# Air_Quality_Sensor_V1_0.net
KiCad netlist of a schematic drawn in EAGLE
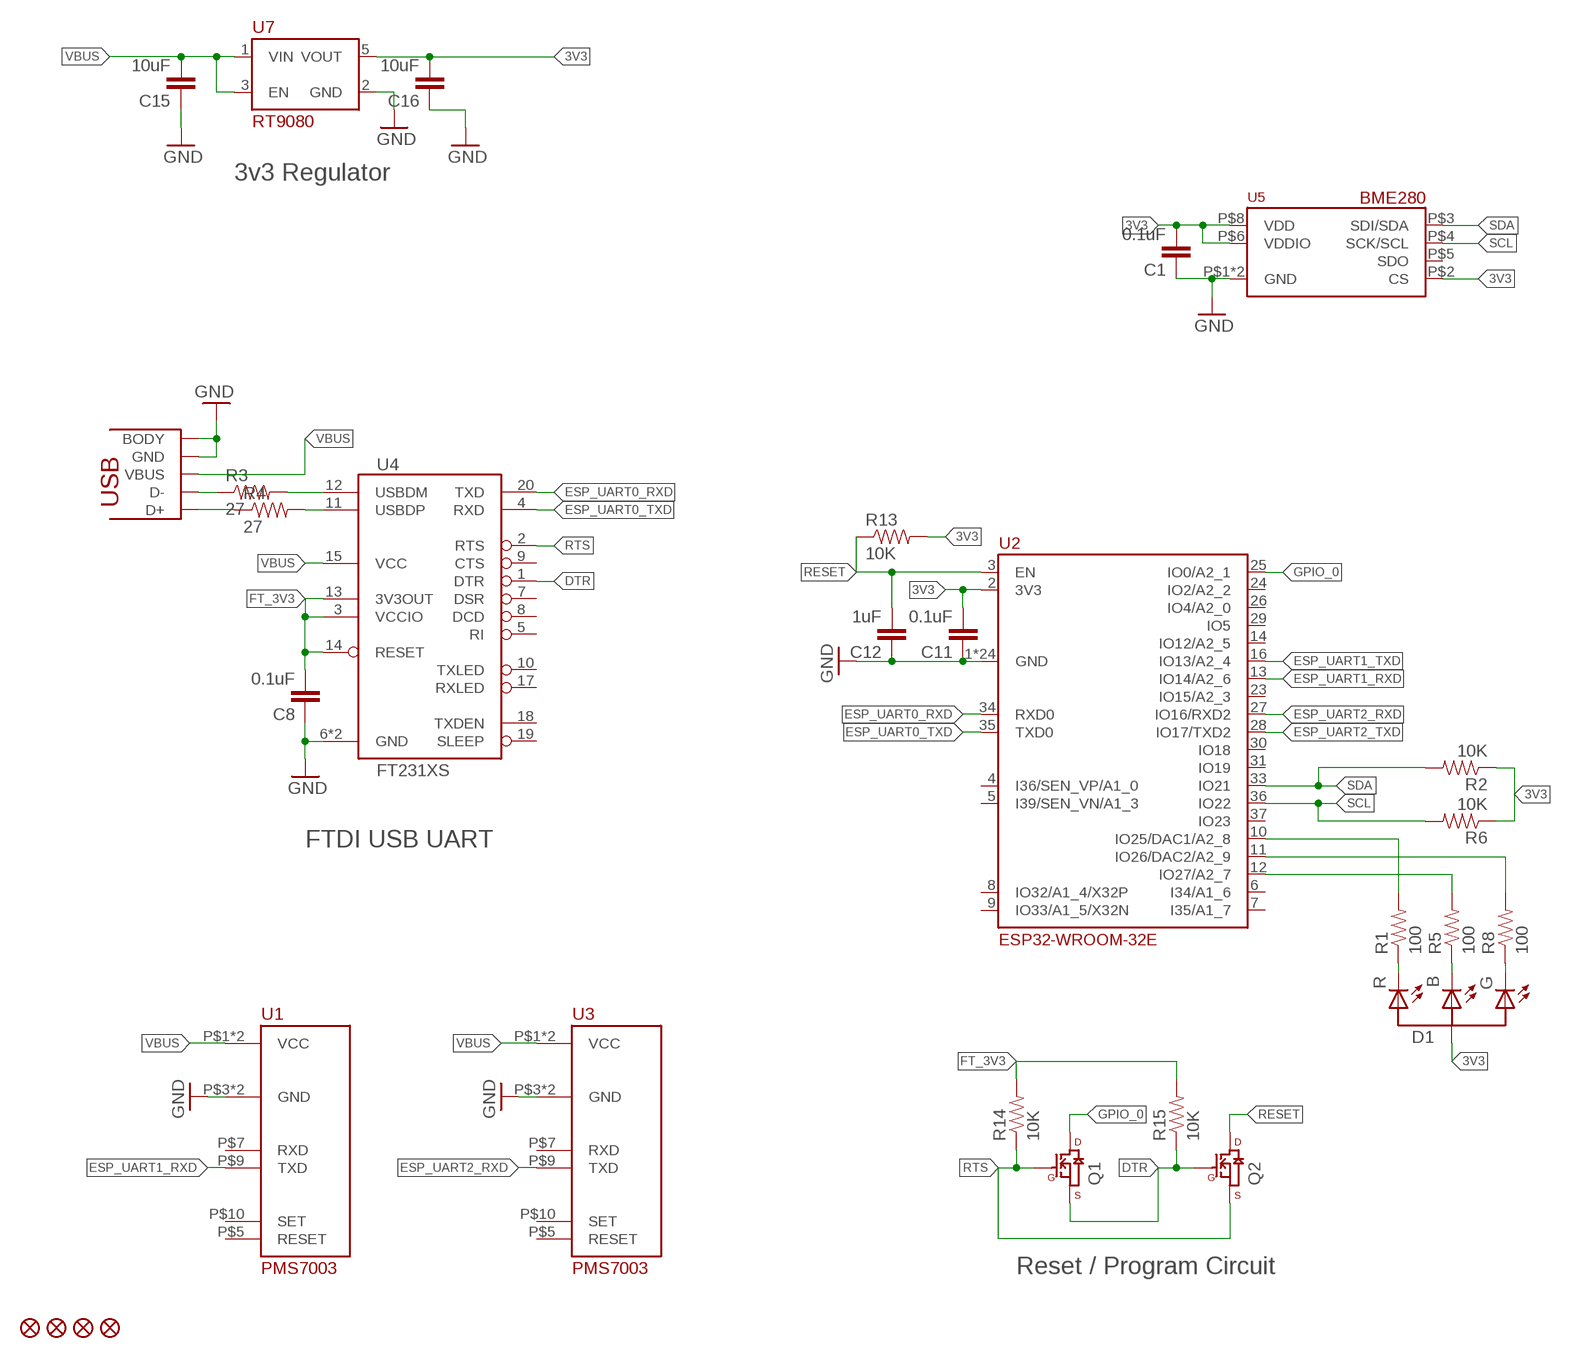
[diagram p0: schematic, sheet 1]

(export (version "E")
  (design (tool "Eeschema 10.0.6"))
  (components
    (comp (ref "C1")
      (value "0.1uF")
      (footprint "eagle-import:0603-CAP")
      (libsource (lib "eagle-import") (part "CAP0603-CAP"))
    )
    (comp (ref "C8")
      (value "0.1uF")
      (footprint "eagle-import:0603-CAP")
      (libsource (lib "eagle-import") (part "CAP0603-CAP"))
    )
    (comp (ref "C11")
      (value "0.1uF")
      (footprint "eagle-import:0603-CAP")
      (libsource (lib "eagle-import") (part "CAP0603-CAP"))
    )
    (comp (ref "C12")
      (value "1uF")
      (footprint "eagle-import:0603-CAP")
      (libsource (lib "eagle-import") (part "CAP0603-CAP"))
    )
    (comp (ref "C15")
      (value "10uF")
      (footprint "eagle-import:1206")
      (libsource (lib "eagle-import") (part "CAP1206"))
    )
    (comp (ref "C16")
      (value "10uF")
      (footprint "eagle-import:1206")
      (libsource (lib "eagle-import") (part "CAP1206"))
    )
    (comp (ref "D1")
      (value "LED_TRICOLOR_COM-ANODE")
      (footprint "eagle-import:LED_1206_SIDE_TRICOLOR")
      (libsource (lib "eagle-import") (part "LED_TRICOLOR_COM-ANODE"))
    )
    (comp (ref "FID1")
      (value "FIDUCIAL")
      (footprint "eagle-import:FIDUCIAL")
      (libsource (lib "eagle-import") (part "FIDUCIAL"))
    )
    (comp (ref "FID2")
      (value "FIDUCIAL")
      (footprint "eagle-import:FIDUCIAL")
      (libsource (lib "eagle-import") (part "FIDUCIAL"))
    )
    (comp (ref "FID3")
      (value "FIDUCIAL")
      (footprint "eagle-import:FIDUCIAL")
      (libsource (lib "eagle-import") (part "FIDUCIAL"))
    )
    (comp (ref "FID4")
      (value "FIDUCIAL")
      (footprint "eagle-import:FIDUCIAL")
      (libsource (lib "eagle-import") (part "FIDUCIAL"))
    )
    (comp (ref "Q1")
      (value "MOSFET_N_CHANNELSI1308")
      (footprint "eagle-import:SC-70-3")
      (libsource (lib "eagle-import") (part "MOSFET_N_CHANNELSI1308"))
    )
    (comp (ref "Q2")
      (value "MOSFET_N_CHANNELSI1308")
      (footprint "eagle-import:SC-70-3")
      (libsource (lib "eagle-import") (part "MOSFET_N_CHANNELSI1308"))
    )
    (comp (ref "R1")
      (value "100")
      (footprint "eagle-import:0603-RES")
      (libsource (lib "eagle-import") (part "RESISTOR0603-RES"))
    )
    (comp (ref "R2")
      (value "10K")
      (footprint "eagle-import:0603-RES")
      (libsource (lib "eagle-import") (part "RESISTOR0603-RES"))
    )
    (comp (ref "R3")
      (value "27")
      (footprint "eagle-import:0603-RES")
      (libsource (lib "eagle-import") (part "RESISTOR0603-RES"))
    )
    (comp (ref "R4")
      (value "27")
      (footprint "eagle-import:0603-RES")
      (libsource (lib "eagle-import") (part "RESISTOR0603-RES"))
    )
    (comp (ref "R5")
      (value "100")
      (footprint "eagle-import:0603-RES")
      (libsource (lib "eagle-import") (part "RESISTOR0603-RES"))
    )
    (comp (ref "R6")
      (value "10K")
      (footprint "eagle-import:0603-RES")
      (libsource (lib "eagle-import") (part "RESISTOR0603-RES"))
    )
    (comp (ref "R8")
      (value "100")
      (footprint "eagle-import:0603-RES")
      (libsource (lib "eagle-import") (part "RESISTOR0603-RES"))
    )
    (comp (ref "R13")
      (value "10K")
      (footprint "eagle-import:0603-RES")
      (libsource (lib "eagle-import") (part "RESISTOR0603-RES"))
    )
    (comp (ref "R14")
      (value "10K")
      (footprint "eagle-import:0603-RES")
      (libsource (lib "eagle-import") (part "RESISTOR0603-RES"))
    )
    (comp (ref "R15")
      (value "10K")
      (footprint "eagle-import:0603-RES")
      (libsource (lib "eagle-import") (part "RESISTOR0603-RES"))
    )
    (comp (ref "U$1")
      (value "USB-MICROB")
      (footprint "eagle-import:USB-MICROB-10118192")
      (libsource (lib "eagle-import") (part "USB-MICROB"))
    )
    (comp (ref "U1")
      (value "PMS7003_SMD")
      (footprint "eagle-import:PMS7003_SMD")
      (libsource (lib "eagle-import") (part "PMS7003_SMD"))
    )
    (comp (ref "U2")
      (value "ESP32-WROOM-32E")
      (footprint "eagle-import:ESP32-WROOM-32E")
      (libsource (lib "eagle-import") (part "ESP32-WROOM-32E"))
    )
    (comp (ref "U3")
      (value "PMS7003_SMD")
      (footprint "eagle-import:PMS7003_SMD")
      (libsource (lib "eagle-import") (part "PMS7003_SMD"))
    )
    (comp (ref "U4")
      (value "FT231XS")
      (footprint "eagle-import:SSOP-20")
      (libsource (lib "eagle-import") (part "FT231XS"))
    )
    (comp (ref "U5")
      (value "BME280")
      (footprint "eagle-import:8-VFLGA")
      (libsource (lib "eagle-import") (part "BME280"))
    )
    (comp (ref "U7")
      (value "RT9080")
      (footprint "eagle-import:SOT-23-5")
      (libsource (lib "eagle-import") (part "RT9080"))
    )
  )
  (nets
    (net (code "1") (name "3V3") (class "Default")
      (node (ref "C1") (pin "2") (pinfunction "2_2") (pintype "passive"))
      (node (ref "C11") (pin "2") (pinfunction "2_2") (pintype "passive"))
      (node (ref "C16") (pin "2") (pinfunction "2_2") (pintype "passive"))
      (node (ref "D1") (pin "P$3") (pinfunction "A_P$3") (pintype "passive"))
      (node (ref "R13") (pin "2") (pinfunction "2_2") (pintype "passive"))
      (node (ref "R2") (pin "1") (pinfunction "1_1") (pintype "passive"))
      (node (ref "R6") (pin "1") (pinfunction "1_1") (pintype "passive"))
      (node (ref "U2") (pin "2") (pinfunction "3V3_2") (pintype "power_in"))
      (node (ref "U5") (pin "P$2") (pinfunction "CS_P$2") (pintype "bidirectional"))
      (node (ref "U5") (pin "P$6") (pinfunction "VDDIO_P$6") (pintype "bidirectional"))
      (node (ref "U5") (pin "P$8") (pinfunction "VDD_P$8") (pintype "bidirectional"))
      (node (ref "U7") (pin "5") (pinfunction "VOUT_5") (pintype "bidirectional"))
    )
    (net (code "2") (name "DTR") (class "Default")
      (node (ref "Q1") (pin "P$2") (pinfunction "S_P$2") (pintype "bidirectional"))
      (node (ref "Q2") (pin "P$1") (pinfunction "G_P$1") (pintype "bidirectional"))
      (node (ref "R15") (pin "1") (pinfunction "1_1") (pintype "passive"))
      (node (ref "U4") (pin "1") (pinfunction "DTR_1") (pintype "output"))
    )
    (net (code "3") (name "ESP_UART0_RXD") (class "Default")
      (node (ref "U2") (pin "34") (pinfunction "RXD0_34") (pintype "bidirectional"))
      (node (ref "U4") (pin "20") (pinfunction "TXD_20") (pintype "output"))
    )
    (net (code "4") (name "ESP_UART0_TXD") (class "Default")
      (node (ref "U2") (pin "35") (pinfunction "TXD0_35") (pintype "bidirectional"))
      (node (ref "U4") (pin "4") (pinfunction "RXD_4") (pintype "input"))
    )
    (net (code "5") (name "ESP_UART1_RXD") (class "Default")
      (node (ref "U1") (pin "P$9") (pinfunction "TXD_P$9") (pintype "bidirectional"))
      (node (ref "U2") (pin "13") (pinfunction "IO14/A2_6_13") (pintype "bidirectional"))
    )
    (net (code "6") (name "ESP_UART1_TXD") (class "Default")
      (node (ref "U2") (pin "16") (pinfunction "IO13/A2_4_16") (pintype "bidirectional"))
    )
    (net (code "7") (name "ESP_UART2_RXD") (class "Default")
      (node (ref "U2") (pin "27") (pinfunction "IO16/RXD2_27") (pintype "bidirectional"))
      (node (ref "U3") (pin "P$9") (pinfunction "TXD_P$9") (pintype "bidirectional"))
    )
    (net (code "8") (name "ESP_UART2_TXD") (class "Default")
      (node (ref "U2") (pin "28") (pinfunction "IO17/TXD2_28") (pintype "bidirectional"))
    )
    (net (code "9") (name "FT_3V3") (class "Default")
      (node (ref "C8") (pin "2") (pinfunction "2_2") (pintype "passive"))
      (node (ref "R14") (pin "2") (pinfunction "2_2") (pintype "passive"))
      (node (ref "R15") (pin "2") (pinfunction "2_2") (pintype "passive"))
      (node (ref "U4") (pin "13") (pinfunction "3V3OUT_13") (pintype "output"))
      (node (ref "U4") (pin "14") (pinfunction "RESET_14") (pintype "input"))
      (node (ref "U4") (pin "3") (pinfunction "VCCIO_3") (pintype "power_in"))
    )
    (net (code "10") (name "GND") (class "Default")
      (node (ref "C1") (pin "1") (pinfunction "1_1") (pintype "passive"))
      (node (ref "C11") (pin "1") (pinfunction "1_1") (pintype "passive"))
      (node (ref "C12") (pin "1") (pinfunction "1_1") (pintype "passive"))
      (node (ref "C15") (pin "1") (pinfunction "1_1") (pintype "passive"))
      (node (ref "C16") (pin "1") (pinfunction "1_1") (pintype "passive"))
      (node (ref "C8") (pin "1") (pinfunction "1_1") (pintype "passive"))
      (node (ref "U$1") (pin "5") (pinfunction "GND_5") (pintype "bidirectional"))
      (node (ref "U$1") (pin "BODY@1") (pinfunction "BODY_BODY@1") (pintype "bidirectional"))
      (node (ref "U$1") (pin "BODY@2") (pinfunction "BODY_BODY@2") (pintype "bidirectional"))
      (node (ref "U$1") (pin "BODY@3") (pinfunction "BODY_BODY@3") (pintype "bidirectional"))
      (node (ref "U$1") (pin "BODY@4") (pinfunction "BODY_BODY@4") (pintype "bidirectional"))
      (node (ref "U$1") (pin "BODY@5") (pinfunction "BODY_BODY@5") (pintype "bidirectional"))
      (node (ref "U$1") (pin "BODY@6") (pinfunction "BODY_BODY@6") (pintype "bidirectional"))
      (node (ref "U1") (pin "P$3") (pinfunction "GND_P$3") (pintype "bidirectional"))
      (node (ref "U1") (pin "P$4") (pinfunction "GND_P$4") (pintype "bidirectional"))
      (node (ref "U2") (pin "1") (pinfunction "GND_1") (pintype "power_in"))
      (node (ref "U2") (pin "15") (pinfunction "GND_15") (pintype "power_in"))
      (node (ref "U2") (pin "38") (pinfunction "GND_38") (pintype "power_in"))
      (node (ref "U2") (pin "P$1") (pinfunction "GND_P$1") (pintype "power_in"))
      (node (ref "U2") (pin "P$10") (pinfunction "GND_P$10") (pintype "power_in"))
      (node (ref "U2") (pin "P$11") (pinfunction "GND_P$11") (pintype "power_in"))
      (node (ref "U2") (pin "P$12") (pinfunction "GND_P$12") (pintype "power_in"))
      (node (ref "U2") (pin "P$2") (pinfunction "GND_P$2") (pintype "power_in"))
      (node (ref "U2") (pin "P$3") (pinfunction "GND_P$3") (pintype "power_in"))
      (node (ref "U2") (pin "P$4") (pinfunction "GND_P$4") (pintype "power_in"))
      (node (ref "U2") (pin "P$5") (pinfunction "GND_P$5") (pintype "power_in"))
      (node (ref "U2") (pin "P$6") (pinfunction "GND_P$6") (pintype "power_in"))
      (node (ref "U2") (pin "P$7") (pinfunction "GND_P$7") (pintype "power_in"))
      (node (ref "U2") (pin "P$8") (pinfunction "GND_P$8") (pintype "power_in"))
      (node (ref "U2") (pin "P$9") (pinfunction "GND_P$9") (pintype "power_in"))
      (node (ref "U2") (pin "PAD@1") (pinfunction "GND_PAD@1") (pintype "power_in"))
      (node (ref "U2") (pin "PAD@2") (pinfunction "GND_PAD@2") (pintype "power_in"))
      (node (ref "U2") (pin "PAD@3") (pinfunction "GND_PAD@3") (pintype "power_in"))
      (node (ref "U2") (pin "PAD@4") (pinfunction "GND_PAD@4") (pintype "power_in"))
      (node (ref "U2") (pin "PAD@5") (pinfunction "GND_PAD@5") (pintype "power_in"))
      (node (ref "U2") (pin "PAD@6") (pinfunction "GND_PAD@6") (pintype "power_in"))
      (node (ref "U2") (pin "PAD@7") (pinfunction "GND_PAD@7") (pintype "power_in"))
      (node (ref "U2") (pin "PAD@8") (pinfunction "GND_PAD@8") (pintype "power_in"))
      (node (ref "U2") (pin "PAD@9") (pinfunction "GND_PAD@9") (pintype "power_in"))
      (node (ref "U3") (pin "P$3") (pinfunction "GND_P$3") (pintype "bidirectional"))
      (node (ref "U3") (pin "P$4") (pinfunction "GND_P$4") (pintype "bidirectional"))
      (node (ref "U4") (pin "16") (pinfunction "GND_16") (pintype "power_in"))
      (node (ref "U4") (pin "6") (pinfunction "GND_6") (pintype "power_in"))
      (node (ref "U5") (pin "P$1") (pinfunction "GND_P$1") (pintype "bidirectional"))
      (node (ref "U5") (pin "P$7") (pinfunction "GND_P$7") (pintype "bidirectional"))
      (node (ref "U7") (pin "2") (pinfunction "GND_2") (pintype "bidirectional"))
    )
    (net (code "11") (name "GPIO_0") (class "Default")
      (node (ref "Q1") (pin "P$3") (pinfunction "D_P$3") (pintype "bidirectional"))
      (node (ref "U2") (pin "25") (pinfunction "IO0/A2_1_25") (pintype "bidirectional"))
    )
    (net (code "12") (name "Net-(D1-C_BLU)") (class "Default")
      (node (ref "D1") (pin "P$2") (pinfunction "C_BLU_P$2") (pintype "passive"))
      (node (ref "R5") (pin "1") (pinfunction "1_1") (pintype "passive"))
    )
    (net (code "13") (name "Net-(D1-C_GRN)") (class "Default")
      (node (ref "D1") (pin "P$1") (pinfunction "C_GRN_P$1") (pintype "passive"))
      (node (ref "R8") (pin "1") (pinfunction "1_1") (pintype "passive"))
    )
    (net (code "14") (name "Net-(D1-C_RED)") (class "Default")
      (node (ref "D1") (pin "P$4") (pinfunction "C_RED_P$4") (pintype "passive"))
      (node (ref "R1") (pin "1") (pinfunction "1_1") (pintype "passive"))
    )
    (net (code "15") (name "Net-(U$1-D+)") (class "Default")
      (node (ref "R4") (pin "1") (pinfunction "1_1") (pintype "passive"))
      (node (ref "U$1") (pin "3") (pinfunction "D+_3") (pintype "bidirectional"))
    )
    (net (code "16") (name "Net-(U$1-D-)") (class "Default")
      (node (ref "R3") (pin "1") (pinfunction "1_1") (pintype "passive"))
      (node (ref "U$1") (pin "2") (pinfunction "D-_2") (pintype "bidirectional"))
    )
    (net (code "17") (name "Net-(U2-IO25{slash}DAC1{slash}A2_8)") (class "Default")
      (node (ref "R1") (pin "2") (pinfunction "2_2") (pintype "passive"))
      (node (ref "U2") (pin "10") (pinfunction "IO25/DAC1/A2_8_10") (pintype "bidirectional"))
    )
    (net (code "18") (name "Net-(U2-IO26{slash}DAC2{slash}A2_9)") (class "Default")
      (node (ref "R8") (pin "2") (pinfunction "2_2") (pintype "passive"))
      (node (ref "U2") (pin "11") (pinfunction "IO26/DAC2/A2_9_11") (pintype "bidirectional"))
    )
    (net (code "19") (name "Net-(U2-IO27{slash}A2_7)") (class "Default")
      (node (ref "R5") (pin "2") (pinfunction "2_2") (pintype "passive"))
      (node (ref "U2") (pin "12") (pinfunction "IO27/A2_7_12") (pintype "bidirectional"))
    )
    (net (code "20") (name "Net-(U4-USBDM)") (class "Default")
      (node (ref "R3") (pin "2") (pinfunction "2_2") (pintype "passive"))
      (node (ref "U4") (pin "12") (pinfunction "USBDM_12") (pintype "bidirectional"))
    )
    (net (code "21") (name "Net-(U4-USBDP)") (class "Default")
      (node (ref "R4") (pin "2") (pinfunction "2_2") (pintype "passive"))
      (node (ref "U4") (pin "11") (pinfunction "USBDP_11") (pintype "bidirectional"))
    )
    (net (code "22") (name "RESET") (class "Default")
      (node (ref "C12") (pin "2") (pinfunction "2_2") (pintype "passive"))
      (node (ref "Q2") (pin "P$3") (pinfunction "D_P$3") (pintype "bidirectional"))
      (node (ref "R13") (pin "1") (pinfunction "1_1") (pintype "passive"))
      (node (ref "U2") (pin "3") (pinfunction "EN_3") (pintype "input"))
    )
    (net (code "23") (name "RTS") (class "Default")
      (node (ref "Q1") (pin "P$1") (pinfunction "G_P$1") (pintype "bidirectional"))
      (node (ref "Q2") (pin "P$2") (pinfunction "S_P$2") (pintype "bidirectional"))
      (node (ref "R14") (pin "1") (pinfunction "1_1") (pintype "passive"))
      (node (ref "U4") (pin "2") (pinfunction "RTS_2") (pintype "output"))
    )
    (net (code "24") (name "SCL") (class "Default")
      (node (ref "R6") (pin "2") (pinfunction "2_2") (pintype "passive"))
      (node (ref "U2") (pin "36") (pinfunction "IO22_36") (pintype "bidirectional"))
      (node (ref "U5") (pin "P$4") (pinfunction "SCK/SCL_P$4") (pintype "bidirectional"))
    )
    (net (code "25") (name "SDA") (class "Default")
      (node (ref "R2") (pin "2") (pinfunction "2_2") (pintype "passive"))
      (node (ref "U2") (pin "33") (pinfunction "IO21_33") (pintype "bidirectional"))
      (node (ref "U5") (pin "P$3") (pinfunction "SDI/SDA_P$3") (pintype "bidirectional"))
    )
    (net (code "26") (name "VBUS") (class "Default")
      (node (ref "C15") (pin "2") (pinfunction "2_2") (pintype "passive"))
      (node (ref "U$1") (pin "1") (pinfunction "VBUS_1") (pintype "bidirectional"))
      (node (ref "U1") (pin "P$1") (pinfunction "VCC_P$1") (pintype "bidirectional"))
      (node (ref "U1") (pin "P$2") (pinfunction "VCC_P$2") (pintype "bidirectional"))
      (node (ref "U3") (pin "P$1") (pinfunction "VCC_P$1") (pintype "bidirectional"))
      (node (ref "U3") (pin "P$2") (pinfunction "VCC_P$2") (pintype "bidirectional"))
      (node (ref "U4") (pin "15") (pinfunction "VCC_15") (pintype "power_in"))
      (node (ref "U7") (pin "1") (pinfunction "VIN_1") (pintype "bidirectional"))
      (node (ref "U7") (pin "3") (pinfunction "EN_3") (pintype "bidirectional"))
    )
    (net (code "27") (name "unconnected-(U1-RESET-PadP$5)") (class "Default")
      (node (ref "U1") (pin "P$5") (pinfunction "RESET_P$5") (pintype "bidirectional"))
    )
    (net (code "28") (name "unconnected-(U1-RXD-PadP$7)") (class "Default")
      (node (ref "U1") (pin "P$7") (pinfunction "RXD_P$7") (pintype "bidirectional"))
    )
    (net (code "29") (name "unconnected-(U1-SET-PadP$10)") (class "Default")
      (node (ref "U1") (pin "P$10") (pinfunction "SET_P$10") (pintype "bidirectional"))
    )
    (net (code "30") (name "unconnected-(U2-I34{slash}A1_6-Pad6)") (class "Default")
      (node (ref "U2") (pin "6") (pinfunction "I34/A1_6_6") (pintype "input"))
    )
    (net (code "31") (name "unconnected-(U2-I35{slash}A1_7-Pad7)") (class "Default")
      (node (ref "U2") (pin "7") (pinfunction "I35/A1_7_7") (pintype "input"))
    )
    (net (code "32") (name "unconnected-(U2-I36{slash}SEN_VP{slash}A1_0-Pad4)") (class "Default")
      (node (ref "U2") (pin "4") (pinfunction "I36/SEN_VP/A1_0_4") (pintype "input"))
    )
    (net (code "33") (name "unconnected-(U2-I39{slash}SEN_VN{slash}A1_3-Pad5)") (class "Default")
      (node (ref "U2") (pin "5") (pinfunction "I39/SEN_VN/A1_3_5") (pintype "input"))
    )
    (net (code "34") (name "unconnected-(U2-IO2{slash}A2_2-Pad24)") (class "Default")
      (node (ref "U2") (pin "24") (pinfunction "IO2/A2_2_24") (pintype "bidirectional"))
    )
    (net (code "35") (name "unconnected-(U2-IO4{slash}A2_0-Pad26)") (class "Default")
      (node (ref "U2") (pin "26") (pinfunction "IO4/A2_0_26") (pintype "bidirectional"))
    )
    (net (code "36") (name "unconnected-(U2-IO5-Pad29)") (class "Default")
      (node (ref "U2") (pin "29") (pinfunction "IO5_29") (pintype "bidirectional"))
    )
    (net (code "37") (name "unconnected-(U2-IO12{slash}A2_5-Pad14)") (class "Default")
      (node (ref "U2") (pin "14") (pinfunction "IO12/A2_5_14") (pintype "bidirectional"))
    )
    (net (code "38") (name "unconnected-(U2-IO15{slash}A2_3-Pad23)") (class "Default")
      (node (ref "U2") (pin "23") (pinfunction "IO15/A2_3_23") (pintype "bidirectional"))
    )
    (net (code "39") (name "unconnected-(U2-IO18-Pad30)") (class "Default")
      (node (ref "U2") (pin "30") (pinfunction "IO18_30") (pintype "bidirectional"))
    )
    (net (code "40") (name "unconnected-(U2-IO19-Pad31)") (class "Default")
      (node (ref "U2") (pin "31") (pinfunction "IO19_31") (pintype "bidirectional"))
    )
    (net (code "41") (name "unconnected-(U2-IO23-Pad37)") (class "Default")
      (node (ref "U2") (pin "37") (pinfunction "IO23_37") (pintype "bidirectional"))
    )
    (net (code "42") (name "unconnected-(U2-IO32{slash}A1_4{slash}X32P-Pad8)") (class "Default")
      (node (ref "U2") (pin "8") (pinfunction "IO32/A1_4/X32P_8") (pintype "bidirectional"))
    )
    (net (code "43") (name "unconnected-(U2-IO33{slash}A1_5{slash}X32N-Pad9)") (class "Default")
      (node (ref "U2") (pin "9") (pinfunction "IO33/A1_5/X32N_9") (pintype "bidirectional"))
    )
    (net (code "44") (name "unconnected-(U3-RESET-PadP$5)") (class "Default")
      (node (ref "U3") (pin "P$5") (pinfunction "RESET_P$5") (pintype "bidirectional"))
    )
    (net (code "45") (name "unconnected-(U3-RXD-PadP$7)") (class "Default")
      (node (ref "U3") (pin "P$7") (pinfunction "RXD_P$7") (pintype "bidirectional"))
    )
    (net (code "46") (name "unconnected-(U3-SET-PadP$10)") (class "Default")
      (node (ref "U3") (pin "P$10") (pinfunction "SET_P$10") (pintype "bidirectional"))
    )
    (net (code "47") (name "unconnected-(U4-CTS-Pad9)") (class "Default")
      (node (ref "U4") (pin "9") (pinfunction "CTS_9") (pintype "input"))
    )
    (net (code "48") (name "unconnected-(U4-DCD-Pad8)") (class "Default")
      (node (ref "U4") (pin "8") (pinfunction "DCD_8") (pintype "input"))
    )
    (net (code "49") (name "unconnected-(U4-DSR-Pad7)") (class "Default")
      (node (ref "U4") (pin "7") (pinfunction "DSR_7") (pintype "input"))
    )
    (net (code "50") (name "unconnected-(U4-RI-Pad5)") (class "Default")
      (node (ref "U4") (pin "5") (pinfunction "RI_5") (pintype "input"))
    )
    (net (code "51") (name "unconnected-(U4-RXLED-Pad17)") (class "Default")
      (node (ref "U4") (pin "17") (pinfunction "RXLED_17") (pintype "input"))
    )
    (net (code "52") (name "unconnected-(U4-SLEEP-Pad19)") (class "Default")
      (node (ref "U4") (pin "19") (pinfunction "SLEEP_19") (pintype "input"))
    )
    (net (code "53") (name "unconnected-(U4-TXDEN-Pad18)") (class "Default")
      (node (ref "U4") (pin "18") (pinfunction "TXDEN_18") (pintype "input"))
    )
    (net (code "54") (name "unconnected-(U4-TXLED-Pad10)") (class "Default")
      (node (ref "U4") (pin "10") (pinfunction "TXLED_10") (pintype "input"))
    )
    (net (code "55") (name "unconnected-(U5-SDO-PadP$5)") (class "Default")
      (node (ref "U5") (pin "P$5") (pinfunction "SDO_P$5") (pintype "bidirectional"))
    )
  )
)
